# Sheet6.net
KiCad netlist of a schematic drawn in Altium Designer
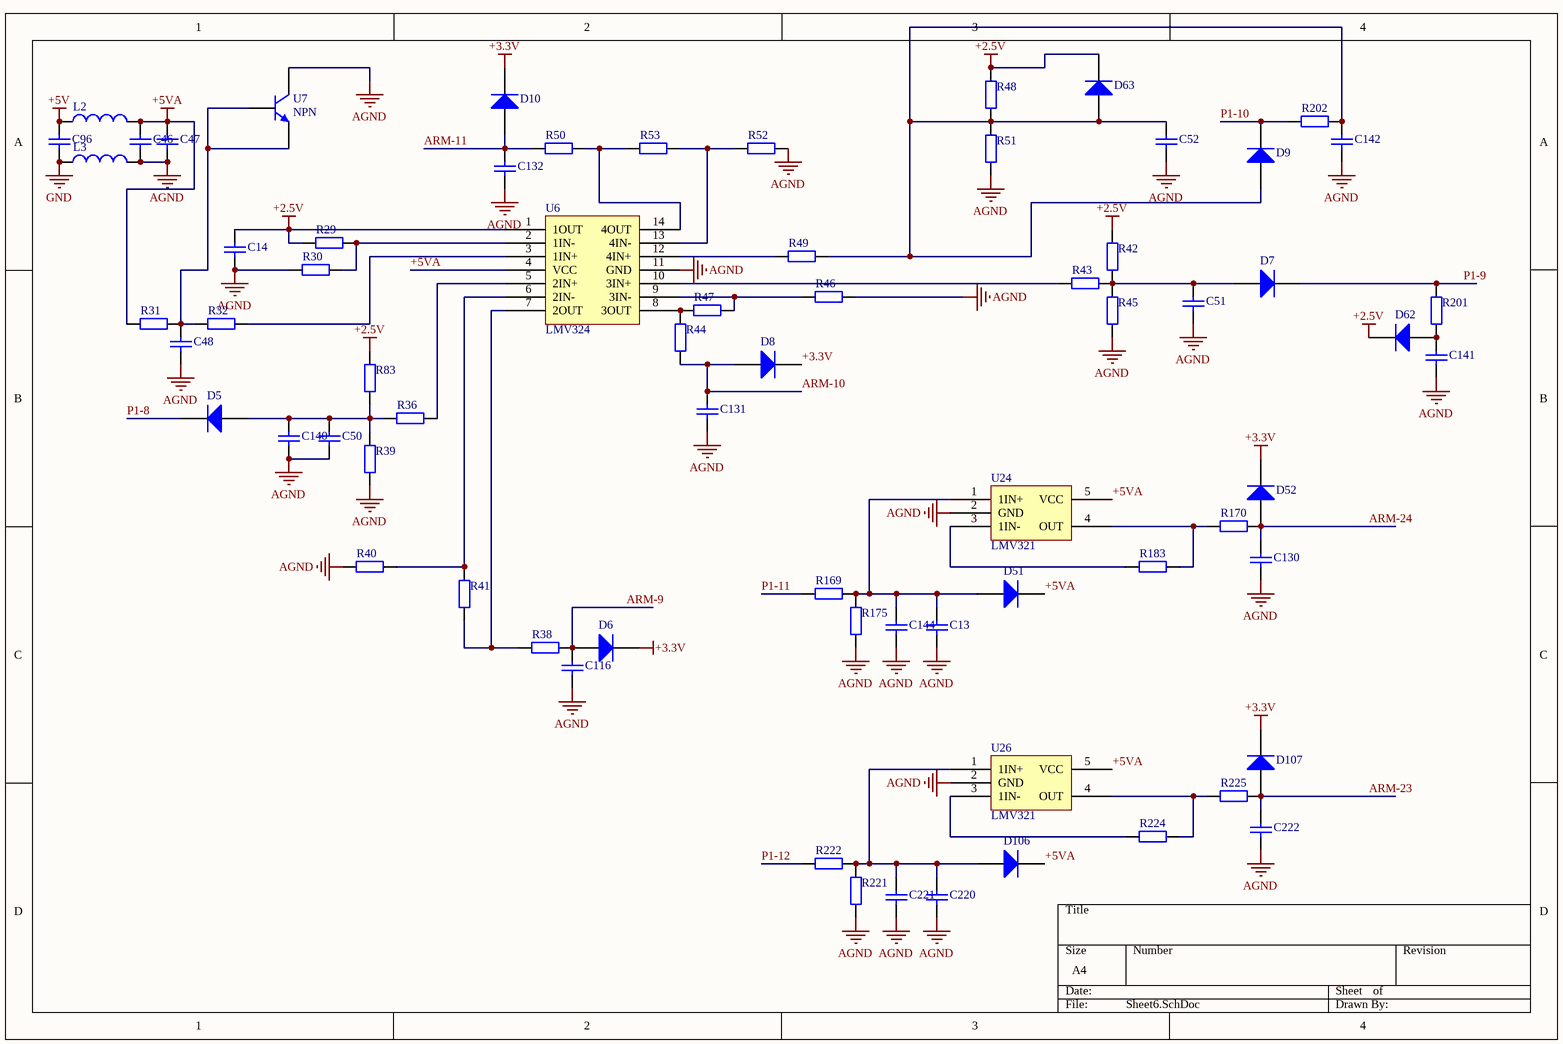
[diagram p0: Sheet6.SchDoc]

(export (version "E")
  (design (tool "Eeschema 10.0.6"))
  (components
    (comp (ref "C13")
      (value "Cap")
      (footprint "RAD-0.3")
      (description "Capacitor")
      (fields (field (name "PUBLISHER") "Altium Limited"))
      (libsource (lib "Miscellaneous Devices") (part "Cap"))
    )
    (comp (ref "C14")
      (value "Cap")
      (footprint "RAD-0.3")
      (description "Capacitor")
      (fields (field (name "PUBLISHER") "Altium Limited"))
      (libsource (lib "Miscellaneous Devices") (part "Cap"))
    )
    (comp (ref "C46")
      (value "Cap")
      (footprint "RAD-0.3")
      (description "Capacitor")
      (fields (field (name "PUBLISHER") "Altium Limited"))
      (libsource (lib "Miscellaneous Devices") (part "Cap"))
    )
    (comp (ref "C47")
      (value "Cap")
      (footprint "RAD-0.3")
      (description "Capacitor")
      (fields (field (name "PUBLISHER") "Altium Limited"))
      (libsource (lib "Miscellaneous Devices") (part "Cap"))
    )
    (comp (ref "C48")
      (value "Cap")
      (footprint "RAD-0.3")
      (description "Capacitor")
      (fields (field (name "PUBLISHER") "Altium Limited"))
      (libsource (lib "Miscellaneous Devices") (part "Cap"))
    )
    (comp (ref "C50")
      (value "Cap")
      (footprint "RAD-0.3")
      (description "Capacitor")
      (fields (field (name "PUBLISHER") "Altium Limited"))
      (libsource (lib "Miscellaneous Devices") (part "Cap"))
    )
    (comp (ref "C51")
      (value "Cap")
      (footprint "RAD-0.3")
      (description "Capacitor")
      (fields (field (name "PUBLISHER") "Altium Limited"))
      (libsource (lib "Miscellaneous Devices") (part "Cap"))
    )
    (comp (ref "C52")
      (value "Cap")
      (footprint "RAD-0.3")
      (description "Capacitor")
      (fields (field (name "PUBLISHER") "Altium Limited"))
      (libsource (lib "Miscellaneous Devices") (part "Cap"))
    )
    (comp (ref "C96")
      (value "Cap")
      (footprint "RAD-0.3")
      (description "Capacitor")
      (fields (field (name "PUBLISHER") "Altium Limited"))
      (libsource (lib "Miscellaneous Devices") (part "Cap"))
    )
    (comp (ref "C116")
      (value "Cap")
      (footprint "RAD-0.3")
      (description "Capacitor")
      (fields (field (name "PUBLISHER") "Altium Limited"))
      (libsource (lib "Miscellaneous Devices") (part "Cap"))
    )
    (comp (ref "C130")
      (value "Cap")
      (footprint "RAD-0.3")
      (description "Capacitor")
      (fields (field (name "PUBLISHER") "Altium Limited"))
      (libsource (lib "Miscellaneous Devices") (part "Cap"))
    )
    (comp (ref "C131")
      (value "Cap")
      (footprint "RAD-0.3")
      (description "Capacitor")
      (fields (field (name "PUBLISHER") "Altium Limited"))
      (libsource (lib "Miscellaneous Devices") (part "Cap"))
    )
    (comp (ref "C132")
      (value "Cap")
      (footprint "RAD-0.3")
      (description "Capacitor")
      (fields (field (name "PUBLISHER") "Altium Limited"))
      (libsource (lib "Miscellaneous Devices") (part "Cap"))
    )
    (comp (ref "C140")
      (value "Cap")
      (footprint "RAD-0.3")
      (description "Capacitor")
      (fields (field (name "PUBLISHER") "Altium Limited"))
      (libsource (lib "Miscellaneous Devices") (part "Cap"))
    )
    (comp (ref "C141")
      (value "Cap")
      (footprint "RAD-0.3")
      (description "Capacitor")
      (fields (field (name "PUBLISHER") "Altium Limited"))
      (libsource (lib "Miscellaneous Devices") (part "Cap"))
    )
    (comp (ref "C142")
      (value "Cap")
      (footprint "RAD-0.3")
      (description "Capacitor")
      (fields (field (name "PUBLISHER") "Altium Limited"))
      (libsource (lib "Miscellaneous Devices") (part "Cap"))
    )
    (comp (ref "C144")
      (value "Cap")
      (footprint "RAD-0.3")
      (description "Capacitor")
      (fields (field (name "PUBLISHER") "Altium Limited"))
      (libsource (lib "Miscellaneous Devices") (part "Cap"))
    )
    (comp (ref "C220")
      (value "Cap")
      (footprint "RAD-0.3")
      (description "Capacitor")
      (fields (field (name "PUBLISHER") "Altium Limited"))
      (libsource (lib "Miscellaneous Devices") (part "Cap"))
    )
    (comp (ref "C221")
      (value "Cap")
      (footprint "RAD-0.3")
      (description "Capacitor")
      (fields (field (name "PUBLISHER") "Altium Limited"))
      (libsource (lib "Miscellaneous Devices") (part "Cap"))
    )
    (comp (ref "C222")
      (value "Cap")
      (footprint "RAD-0.3")
      (description "Capacitor")
      (fields (field (name "PUBLISHER") "Altium Limited"))
      (libsource (lib "Miscellaneous Devices") (part "Cap"))
    )
    (comp (ref "D5")
      (value "Diode 1N4007")
      (footprint "DO-41")
      (description "1 Amp General Purpose Rectifier")
      (fields (field (name "PUBLISHER") "Altium Limited"))
      (libsource (lib "Miscellaneous Devices") (part "Diode 1N4007"))
    )
    (comp (ref "D6")
      (value "Diode 1N4007")
      (footprint "DO-41")
      (description "1 Amp General Purpose Rectifier")
      (fields (field (name "PUBLISHER") "Altium Limited"))
      (libsource (lib "Miscellaneous Devices") (part "Diode 1N4007"))
    )
    (comp (ref "D7")
      (value "Diode 1N4007")
      (footprint "DO-41")
      (description "1 Amp General Purpose Rectifier")
      (fields (field (name "PUBLISHER") "Altium Limited"))
      (libsource (lib "Miscellaneous Devices") (part "Diode 1N4007"))
    )
    (comp (ref "D8")
      (value "Diode 1N4007")
      (footprint "DO-41")
      (description "1 Amp General Purpose Rectifier")
      (fields (field (name "PUBLISHER") "Altium Limited"))
      (libsource (lib "Miscellaneous Devices") (part "Diode 1N4007"))
    )
    (comp (ref "D9")
      (value "Diode 1N4007")
      (footprint "DO-41")
      (description "1 Amp General Purpose Rectifier")
      (fields (field (name "PUBLISHER") "Altium Limited"))
      (libsource (lib "Miscellaneous Devices") (part "Diode 1N4007"))
    )
    (comp (ref "D10")
      (value "Diode 1N4007")
      (footprint "DO-41")
      (description "1 Amp General Purpose Rectifier")
      (fields (field (name "PUBLISHER") "Altium Limited"))
      (libsource (lib "Miscellaneous Devices") (part "Diode 1N4007"))
    )
    (comp (ref "D51")
      (value "Diode 1N4007")
      (footprint "DO-41")
      (description "1 Amp General Purpose Rectifier")
      (fields (field (name "PUBLISHER") "Altium Limited"))
      (libsource (lib "Miscellaneous Devices") (part "Diode 1N4007"))
    )
    (comp (ref "D52")
      (value "Diode 1N4007")
      (footprint "DO-41")
      (description "1 Amp General Purpose Rectifier")
      (fields (field (name "PUBLISHER") "Altium Limited"))
      (libsource (lib "Miscellaneous Devices") (part "Diode 1N4007"))
    )
    (comp (ref "D62")
      (value "Diode 1N4007")
      (footprint "DO-41")
      (description "1 Amp General Purpose Rectifier")
      (fields (field (name "PUBLISHER") "Altium Limited"))
      (libsource (lib "Miscellaneous Devices") (part "Diode 1N4007"))
    )
    (comp (ref "D63")
      (value "Diode 1N4007")
      (footprint "DO-41")
      (description "1 Amp General Purpose Rectifier")
      (fields (field (name "PUBLISHER") "Altium Limited"))
      (libsource (lib "Miscellaneous Devices") (part "Diode 1N4007"))
    )
    (comp (ref "D106")
      (value "Diode 1N4007")
      (footprint "DO-41")
      (description "1 Amp General Purpose Rectifier")
      (fields (field (name "PUBLISHER") "Altium Limited"))
      (libsource (lib "Miscellaneous Devices") (part "Diode 1N4007"))
    )
    (comp (ref "D107")
      (value "Diode 1N4007")
      (footprint "DO-41")
      (description "1 Amp General Purpose Rectifier")
      (fields (field (name "PUBLISHER") "Altium Limited"))
      (libsource (lib "Miscellaneous Devices") (part "Diode 1N4007"))
    )
    (comp (ref "L2")
      (value "Inductor")
      (footprint "0402-A")
      (fields (field (name "PUBLISHER") "Altium Limited"))
      (libsource (lib "Miscellaneous Devices") (part "Inductor"))
    )
    (comp (ref "L3")
      (value "Inductor")
      (footprint "0402-A")
      (fields (field (name "PUBLISHER") "Altium Limited"))
      (libsource (lib "Miscellaneous Devices") (part "Inductor"))
    )
    (comp (ref "R29")
      (value "Res2")
      (footprint "AXIAL-0.4")
      (description "Resistor")
      (fields (field (name "PUBLISHER") "Altium Limited"))
      (libsource (lib "Miscellaneous Devices") (part "Res2"))
    )
    (comp (ref "R30")
      (value "Res2")
      (footprint "AXIAL-0.4")
      (description "Resistor")
      (fields (field (name "PUBLISHER") "Altium Limited"))
      (libsource (lib "Miscellaneous Devices") (part "Res2"))
    )
    (comp (ref "R31")
      (value "Res2")
      (footprint "AXIAL-0.4")
      (description "Resistor")
      (fields (field (name "PUBLISHER") "Altium Limited"))
      (libsource (lib "Miscellaneous Devices") (part "Res2"))
    )
    (comp (ref "R32")
      (value "Res2")
      (footprint "AXIAL-0.4")
      (description "Resistor")
      (fields (field (name "PUBLISHER") "Altium Limited"))
      (libsource (lib "Miscellaneous Devices") (part "Res2"))
    )
    (comp (ref "R36")
      (value "Res2")
      (footprint "AXIAL-0.4")
      (description "Resistor")
      (fields (field (name "PUBLISHER") "Altium Limited"))
      (libsource (lib "Miscellaneous Devices") (part "Res2"))
    )
    (comp (ref "R38")
      (value "Res2")
      (footprint "AXIAL-0.4")
      (description "Resistor")
      (fields (field (name "PUBLISHER") "Altium Limited"))
      (libsource (lib "") (part "Res2_2"))
    )
    (comp (ref "R39")
      (value "Res2")
      (footprint "AXIAL-0.4")
      (description "Resistor")
      (fields (field (name "PUBLISHER") "Altium Limited"))
      (libsource (lib "") (part "Res2_1"))
    )
    (comp (ref "R40")
      (value "Res2")
      (footprint "AXIAL-0.4")
      (description "Resistor")
      (fields (field (name "PUBLISHER") "Altium Limited"))
      (libsource (lib "Miscellaneous Devices") (part "Res2"))
    )
    (comp (ref "R41")
      (value "Res2")
      (footprint "AXIAL-0.4")
      (description "Resistor")
      (fields (field (name "PUBLISHER") "Altium Limited"))
      (libsource (lib "") (part "Res2_1"))
    )
    (comp (ref "R42")
      (value "Res2")
      (footprint "AXIAL-0.4")
      (description "Resistor")
      (fields (field (name "PUBLISHER") "Altium Limited"))
      (libsource (lib "") (part "Res2_1"))
    )
    (comp (ref "R43")
      (value "Res2")
      (footprint "AXIAL-0.4")
      (description "Resistor")
      (fields (field (name "PUBLISHER") "Altium Limited"))
      (libsource (lib "Miscellaneous Devices") (part "Res2"))
    )
    (comp (ref "R44")
      (value "Res2")
      (footprint "AXIAL-0.4")
      (description "Resistor")
      (fields (field (name "PUBLISHER") "Altium Limited"))
      (libsource (lib "") (part "Res2_1"))
    )
    (comp (ref "R45")
      (value "Res2")
      (footprint "AXIAL-0.4")
      (description "Resistor")
      (fields (field (name "PUBLISHER") "Altium Limited"))
      (libsource (lib "") (part "Res2_1"))
    )
    (comp (ref "R46")
      (value "Res2")
      (footprint "AXIAL-0.4")
      (description "Resistor")
      (fields (field (name "PUBLISHER") "Altium Limited"))
      (libsource (lib "Miscellaneous Devices") (part "Res2"))
    )
    (comp (ref "R47")
      (value "Res2")
      (footprint "AXIAL-0.4")
      (description "Resistor")
      (fields (field (name "PUBLISHER") "Altium Limited"))
      (libsource (lib "Miscellaneous Devices") (part "Res2"))
    )
    (comp (ref "R48")
      (value "Res2")
      (footprint "AXIAL-0.4")
      (description "Resistor")
      (fields (field (name "PUBLISHER") "Altium Limited"))
      (libsource (lib "") (part "Res2_1"))
    )
    (comp (ref "R49")
      (value "Res2")
      (footprint "AXIAL-0.4")
      (description "Resistor")
      (fields (field (name "PUBLISHER") "Altium Limited"))
      (libsource (lib "Miscellaneous Devices") (part "Res2"))
    )
    (comp (ref "R50")
      (value "Res2")
      (footprint "AXIAL-0.4")
      (description "Resistor")
      (fields (field (name "PUBLISHER") "Altium Limited"))
      (libsource (lib "Miscellaneous Devices") (part "Res2"))
    )
    (comp (ref "R51")
      (value "Res2")
      (footprint "AXIAL-0.4")
      (description "Resistor")
      (fields (field (name "PUBLISHER") "Altium Limited"))
      (libsource (lib "") (part "Res2_1"))
    )
    (comp (ref "R52")
      (value "Res2")
      (footprint "AXIAL-0.4")
      (description "Resistor")
      (fields (field (name "PUBLISHER") "Altium Limited"))
      (libsource (lib "Miscellaneous Devices") (part "Res2"))
    )
    (comp (ref "R53")
      (value "Res2")
      (footprint "AXIAL-0.4")
      (description "Resistor")
      (fields (field (name "PUBLISHER") "Altium Limited"))
      (libsource (lib "Miscellaneous Devices") (part "Res2"))
    )
    (comp (ref "R83")
      (value "Res2")
      (footprint "AXIAL-0.4")
      (description "Resistor")
      (fields (field (name "PUBLISHER") "Altium Limited"))
      (libsource (lib "") (part "Res2_1"))
    )
    (comp (ref "R169")
      (value "Res2")
      (footprint "AXIAL-0.4")
      (description "Resistor")
      (fields (field (name "PUBLISHER") "Altium Limited"))
      (libsource (lib "Miscellaneous Devices") (part "Res2"))
    )
    (comp (ref "R170")
      (value "Res2")
      (footprint "AXIAL-0.4")
      (description "Resistor")
      (fields (field (name "PUBLISHER") "Altium Limited"))
      (libsource (lib "Miscellaneous Devices") (part "Res2"))
    )
    (comp (ref "R175")
      (value "Res2")
      (footprint "AXIAL-0.4")
      (description "Resistor")
      (fields (field (name "PUBLISHER") "Altium Limited"))
      (libsource (lib "") (part "Res2_1"))
    )
    (comp (ref "R183")
      (value "Res2")
      (footprint "AXIAL-0.4")
      (description "Resistor")
      (fields (field (name "PUBLISHER") "Altium Limited"))
      (libsource (lib "Miscellaneous Devices") (part "Res2"))
    )
    (comp (ref "R201")
      (value "Res2")
      (footprint "AXIAL-0.4")
      (description "Resistor")
      (fields (field (name "PUBLISHER") "Altium Limited"))
      (libsource (lib "") (part "Res2_1"))
    )
    (comp (ref "R202")
      (value "Res2")
      (footprint "AXIAL-0.4")
      (description "Resistor")
      (fields (field (name "PUBLISHER") "Altium Limited"))
      (libsource (lib "") (part "Res2_2"))
    )
    (comp (ref "R221")
      (value "Res2")
      (footprint "AXIAL-0.4")
      (description "Resistor")
      (fields (field (name "PUBLISHER") "Altium Limited"))
      (libsource (lib "") (part "Res2_1"))
    )
    (comp (ref "R222")
      (value "Res2")
      (footprint "AXIAL-0.4")
      (description "Resistor")
      (fields (field (name "PUBLISHER") "Altium Limited"))
      (libsource (lib "Miscellaneous Devices") (part "Res2"))
    )
    (comp (ref "R224")
      (value "Res2")
      (footprint "AXIAL-0.4")
      (description "Resistor")
      (fields (field (name "PUBLISHER") "Altium Limited"))
      (libsource (lib "Miscellaneous Devices") (part "Res2"))
    )
    (comp (ref "R225")
      (value "Res2")
      (footprint "AXIAL-0.4")
      (description "Resistor")
      (fields (field (name "PUBLISHER") "Altium Limited"))
      (libsource (lib "Miscellaneous Devices") (part "Res2"))
    )
    (comp (ref "U6") (value "LMV324") (libsource (lib "LMV324") (part "Component_1")))
    (comp (ref "U7")
      (value "NPN")
      (footprint "TO-226")
      (description "NPN Bipolar Transistor")
      (fields (field (name "PUBLISHER") "Altium Limited"))
      (libsource (lib "Miscellaneous Devices") (part "NPN"))
    )
    (comp (ref "U24") (value "LMV321") (libsource (lib "LMV321") (part "Component_1")))
    (comp (ref "U26") (value "LMV321") (libsource (lib "LMV321") (part "Component_1")))
  )
  (nets
    (net (code "1") (name "+2.5V") (class "Default")
      (node (ref "C14") (pin "2") (pinfunction "2_2") (pintype "passive"))
      (node (ref "D62") (pin "2") (pinfunction "K_2") (pintype "passive"))
      (node (ref "D63") (pin "2") (pinfunction "K_2") (pintype "passive"))
      (node (ref "R29") (pin "2") (pinfunction "2_2") (pintype "passive"))
      (node (ref "R42") (pin "1") (pinfunction "1_1") (pintype "passive"))
      (node (ref "R48") (pin "1") (pinfunction "1_1") (pintype "passive"))
      (node (ref "R83") (pin "1") (pinfunction "1_1") (pintype "passive"))
      (node (ref "U6") (pin "1") (pinfunction "1OUT_1") (pintype "passive"))
    )
    (net (code "2") (name "+3.3V") (class "Default")
      (node (ref "D10") (pin "2") (pinfunction "K_2") (pintype "passive"))
      (node (ref "D107") (pin "2") (pinfunction "K_2") (pintype "passive"))
      (node (ref "D52") (pin "2") (pinfunction "K_2") (pintype "passive"))
      (node (ref "D6") (pin "2") (pinfunction "K_2") (pintype "passive"))
      (node (ref "D8") (pin "2") (pinfunction "K_2") (pintype "passive"))
    )
    (net (code "3") (name "+5V") (class "Default")
      (node (ref "C96") (pin "2") (pinfunction "2_2") (pintype "passive"))
      (node (ref "L2") (pin "1") (pinfunction "1_1") (pintype "passive"))
    )
    (net (code "4") (name "+5VA") (class "Default")
      (node (ref "C46") (pin "2") (pinfunction "2_2") (pintype "passive"))
      (node (ref "C47") (pin "2") (pinfunction "2_2") (pintype "passive"))
      (node (ref "D106") (pin "2") (pinfunction "K_2") (pintype "passive"))
      (node (ref "D51") (pin "2") (pinfunction "K_2") (pintype "passive"))
      (node (ref "L2") (pin "2") (pinfunction "2_2") (pintype "passive"))
      (node (ref "R31") (pin "2") (pinfunction "2_2") (pintype "passive"))
      (node (ref "U24") (pin "5") (pinfunction "VCC_5") (pintype "passive"))
      (node (ref "U26") (pin "5") (pinfunction "VCC_5") (pintype "passive"))
      (node (ref "U6") (pin "4") (pinfunction "VCC_4") (pintype "passive"))
    )
    (net (code "5") (name "/ARM-9") (class "Default")
      (node (ref "C116") (pin "2") (pinfunction "2_2") (pintype "passive"))
      (node (ref "D6") (pin "1") (pinfunction "A_1") (pintype "passive"))
      (node (ref "R38") (pin "2") (pinfunction "2_2") (pintype "passive"))
    )
    (net (code "6") (name "/ARM-10") (class "Default")
      (node (ref "C131") (pin "2") (pinfunction "2_2") (pintype "passive"))
      (node (ref "D8") (pin "1") (pinfunction "A_1") (pintype "passive"))
      (node (ref "R44") (pin "2") (pinfunction "2_2") (pintype "passive"))
    )
    (net (code "7") (name "/ARM-11") (class "Default")
      (node (ref "C132") (pin "2") (pinfunction "2_2") (pintype "passive"))
      (node (ref "D10") (pin "1") (pinfunction "A_1") (pintype "passive"))
      (node (ref "R50") (pin "2") (pinfunction "2_2") (pintype "passive"))
    )
    (net (code "8") (name "/ARM-23") (class "Default")
      (node (ref "C222") (pin "2") (pinfunction "2_2") (pintype "passive"))
      (node (ref "D107") (pin "1") (pinfunction "A_1") (pintype "passive"))
      (node (ref "R225") (pin "1") (pinfunction "1_1") (pintype "passive"))
    )
    (net (code "9") (name "/ARM-24") (class "Default")
      (node (ref "C130") (pin "2") (pinfunction "2_2") (pintype "passive"))
      (node (ref "D52") (pin "1") (pinfunction "A_1") (pintype "passive"))
      (node (ref "R170") (pin "1") (pinfunction "1_1") (pintype "passive"))
    )
    (net (code "10") (name "/P1-8") (class "Default")
      (node (ref "D5") (pin "2") (pinfunction "K_2") (pintype "passive"))
    )
    (net (code "11") (name "/P1-9") (class "Default")
      (node (ref "D7") (pin "2") (pinfunction "K_2") (pintype "passive"))
      (node (ref "R201") (pin "1") (pinfunction "1_1") (pintype "passive"))
    )
    (net (code "12") (name "/P1-10") (class "Default")
      (node (ref "D9") (pin "2") (pinfunction "K_2") (pintype "passive"))
      (node (ref "R202") (pin "1") (pinfunction "1_1") (pintype "passive"))
    )
    (net (code "13") (name "/P1-11") (class "Default")
      (node (ref "R169") (pin "2") (pinfunction "2_2") (pintype "passive"))
    )
    (net (code "14") (name "/P1-12") (class "Default")
      (node (ref "R222") (pin "2") (pinfunction "2_2") (pintype "passive"))
    )
    (net (code "15") (name "AGND") (class "Default")
      (node (ref "C116") (pin "1") (pinfunction "1_1") (pintype "passive"))
      (node (ref "C13") (pin "1") (pinfunction "1_1") (pintype "passive"))
      (node (ref "C130") (pin "1") (pinfunction "1_1") (pintype "passive"))
      (node (ref "C131") (pin "1") (pinfunction "1_1") (pintype "passive"))
      (node (ref "C132") (pin "1") (pinfunction "1_1") (pintype "passive"))
      (node (ref "C14") (pin "1") (pinfunction "1_1") (pintype "passive"))
      (node (ref "C140") (pin "1") (pinfunction "1_1") (pintype "passive"))
      (node (ref "C141") (pin "1") (pinfunction "1_1") (pintype "passive"))
      (node (ref "C142") (pin "1") (pinfunction "1_1") (pintype "passive"))
      (node (ref "C144") (pin "1") (pinfunction "1_1") (pintype "passive"))
      (node (ref "C220") (pin "1") (pinfunction "1_1") (pintype "passive"))
      (node (ref "C221") (pin "1") (pinfunction "1_1") (pintype "passive"))
      (node (ref "C222") (pin "1") (pinfunction "1_1") (pintype "passive"))
      (node (ref "C46") (pin "1") (pinfunction "1_1") (pintype "passive"))
      (node (ref "C47") (pin "1") (pinfunction "1_1") (pintype "passive"))
      (node (ref "C48") (pin "1") (pinfunction "1_1") (pintype "passive"))
      (node (ref "C50") (pin "1") (pinfunction "1_1") (pintype "passive"))
      (node (ref "C51") (pin "1") (pinfunction "1_1") (pintype "passive"))
      (node (ref "C52") (pin "1") (pinfunction "1_1") (pintype "passive"))
      (node (ref "L3") (pin "2") (pinfunction "2_2") (pintype "passive"))
      (node (ref "R175") (pin "2") (pinfunction "2_2") (pintype "passive"))
      (node (ref "R221") (pin "2") (pinfunction "2_2") (pintype "passive"))
      (node (ref "R30") (pin "2") (pinfunction "2_2") (pintype "passive"))
      (node (ref "R39") (pin "2") (pinfunction "2_2") (pintype "passive"))
      (node (ref "R40") (pin "2") (pinfunction "2_2") (pintype "passive"))
      (node (ref "R45") (pin "2") (pinfunction "2_2") (pintype "passive"))
      (node (ref "R46") (pin "1") (pinfunction "1_1") (pintype "passive"))
      (node (ref "R51") (pin "2") (pinfunction "2_2") (pintype "passive"))
      (node (ref "R52") (pin "1") (pinfunction "1_1") (pintype "passive"))
      (node (ref "U24") (pin "2") (pinfunction "GND_2") (pintype "passive"))
      (node (ref "U26") (pin "2") (pinfunction "GND_2") (pintype "passive"))
      (node (ref "U6") (pin "11") (pinfunction "GND_11") (pintype "passive"))
      (node (ref "U7") (pin "1") (pinfunction "C_1") (pintype "passive"))
    )
    (net (code "16") (name "GND") (class "Default")
      (node (ref "C96") (pin "1") (pinfunction "1_1") (pintype "passive"))
      (node (ref "L3") (pin "1") (pinfunction "1_1") (pintype "passive"))
    )
    (net (code "17") (name "Net-(D5-A)") (class "Default")
      (node (ref "C140") (pin "2") (pinfunction "2_2") (pintype "passive"))
      (node (ref "C50") (pin "2") (pinfunction "2_2") (pintype "passive"))
      (node (ref "D5") (pin "1") (pinfunction "A_1") (pintype "passive"))
      (node (ref "R36") (pin "2") (pinfunction "2_2") (pintype "passive"))
      (node (ref "R39") (pin "1") (pinfunction "1_1") (pintype "passive"))
      (node (ref "R83") (pin "2") (pinfunction "2_2") (pintype "passive"))
    )
    (net (code "18") (name "Net-(D7-A)") (class "Default")
      (node (ref "C51") (pin "2") (pinfunction "2_2") (pintype "passive"))
      (node (ref "D7") (pin "1") (pinfunction "A_1") (pintype "passive"))
      (node (ref "R42") (pin "2") (pinfunction "2_2") (pintype "passive"))
      (node (ref "R43") (pin "1") (pinfunction "1_1") (pintype "passive"))
      (node (ref "R45") (pin "1") (pinfunction "1_1") (pintype "passive"))
    )
    (net (code "19") (name "Net-(D51-A)") (class "Default")
      (node (ref "C13") (pin "2") (pinfunction "2_2") (pintype "passive"))
      (node (ref "C144") (pin "2") (pinfunction "2_2") (pintype "passive"))
      (node (ref "D51") (pin "1") (pinfunction "A_1") (pintype "passive"))
      (node (ref "R169") (pin "1") (pinfunction "1_1") (pintype "passive"))
      (node (ref "R175") (pin "1") (pinfunction "1_1") (pintype "passive"))
      (node (ref "U24") (pin "1") (pinfunction "1IN+_1") (pintype "passive"))
    )
    (net (code "20") (name "Net-(D62-A)") (class "Default")
      (node (ref "C141") (pin "2") (pinfunction "2_2") (pintype "passive"))
      (node (ref "D62") (pin "1") (pinfunction "A_1") (pintype "passive"))
      (node (ref "R201") (pin "2") (pinfunction "2_2") (pintype "passive"))
    )
    (net (code "21") (name "Net-(D63-A)") (class "Default")
      (node (ref "C142") (pin "2") (pinfunction "2_2") (pintype "passive"))
      (node (ref "C52") (pin "2") (pinfunction "2_2") (pintype "passive"))
      (node (ref "D63") (pin "1") (pinfunction "A_1") (pintype "passive"))
      (node (ref "D9") (pin "1") (pinfunction "A_1") (pintype "passive"))
      (node (ref "R202") (pin "2") (pinfunction "2_2") (pintype "passive"))
      (node (ref "R48") (pin "2") (pinfunction "2_2") (pintype "passive"))
      (node (ref "R49") (pin "1") (pinfunction "1_1") (pintype "passive"))
      (node (ref "R51") (pin "1") (pinfunction "1_1") (pintype "passive"))
    )
    (net (code "22") (name "Net-(D106-A)") (class "Default")
      (node (ref "C220") (pin "2") (pinfunction "2_2") (pintype "passive"))
      (node (ref "C221") (pin "2") (pinfunction "2_2") (pintype "passive"))
      (node (ref "D106") (pin "1") (pinfunction "A_1") (pintype "passive"))
      (node (ref "R221") (pin "1") (pinfunction "1_1") (pintype "passive"))
      (node (ref "R222") (pin "1") (pinfunction "1_1") (pintype "passive"))
      (node (ref "U26") (pin "1") (pinfunction "1IN+_1") (pintype "passive"))
    )
    (net (code "23") (name "Net-(U6-1IN+)") (class "Default")
      (node (ref "R32") (pin "1") (pinfunction "1_1") (pintype "passive"))
      (node (ref "U6") (pin "3") (pinfunction "1IN+_3") (pintype "passive"))
    )
    (net (code "24") (name "Net-(U6-1IN-)") (class "Default")
      (node (ref "R29") (pin "1") (pinfunction "1_1") (pintype "passive"))
      (node (ref "R30") (pin "1") (pinfunction "1_1") (pintype "passive"))
      (node (ref "U6") (pin "2") (pinfunction "1IN-_2") (pintype "passive"))
    )
    (net (code "25") (name "Net-(U6-2IN+)") (class "Default")
      (node (ref "R36") (pin "1") (pinfunction "1_1") (pintype "passive"))
      (node (ref "U6") (pin "5") (pinfunction "2IN+_5") (pintype "passive"))
    )
    (net (code "26") (name "Net-(U6-2IN-)") (class "Default")
      (node (ref "R40") (pin "1") (pinfunction "1_1") (pintype "passive"))
      (node (ref "R41") (pin "1") (pinfunction "1_1") (pintype "passive"))
      (node (ref "U6") (pin "6") (pinfunction "2IN-_6") (pintype "passive"))
    )
    (net (code "27") (name "Net-(U6-2OUT)") (class "Default")
      (node (ref "R38") (pin "1") (pinfunction "1_1") (pintype "passive"))
      (node (ref "R41") (pin "2") (pinfunction "2_2") (pintype "passive"))
      (node (ref "U6") (pin "7") (pinfunction "2OUT_7") (pintype "passive"))
    )
    (net (code "28") (name "Net-(U6-3IN+)") (class "Default")
      (node (ref "R43") (pin "2") (pinfunction "2_2") (pintype "passive"))
      (node (ref "U6") (pin "10") (pinfunction "3IN+_10") (pintype "passive"))
    )
    (net (code "29") (name "Net-(U6-3IN-)") (class "Default")
      (node (ref "R46") (pin "2") (pinfunction "2_2") (pintype "passive"))
      (node (ref "R47") (pin "1") (pinfunction "1_1") (pintype "passive"))
      (node (ref "U6") (pin "9") (pinfunction "3IN-_9") (pintype "passive"))
    )
    (net (code "30") (name "Net-(U6-3OUT)") (class "Default")
      (node (ref "R44") (pin "1") (pinfunction "1_1") (pintype "passive"))
      (node (ref "R47") (pin "2") (pinfunction "2_2") (pintype "passive"))
      (node (ref "U6") (pin "8") (pinfunction "3OUT_8") (pintype "passive"))
    )
    (net (code "31") (name "Net-(U6-4IN+)") (class "Default")
      (node (ref "R49") (pin "2") (pinfunction "2_2") (pintype "passive"))
      (node (ref "U6") (pin "12") (pinfunction "4IN+_12") (pintype "passive"))
    )
    (net (code "32") (name "Net-(U6-4IN-)") (class "Default")
      (node (ref "R52") (pin "2") (pinfunction "2_2") (pintype "passive"))
      (node (ref "R53") (pin "1") (pinfunction "1_1") (pintype "passive"))
      (node (ref "U6") (pin "13") (pinfunction "4IN-_13") (pintype "passive"))
    )
    (net (code "33") (name "Net-(U6-4OUT)") (class "Default")
      (node (ref "R50") (pin "1") (pinfunction "1_1") (pintype "passive"))
      (node (ref "R53") (pin "2") (pinfunction "2_2") (pintype "passive"))
      (node (ref "U6") (pin "14") (pinfunction "4OUT_14") (pintype "passive"))
    )
    (net (code "34") (name "Net-(U7-B)") (class "Default")
      (node (ref "C48") (pin "2") (pinfunction "2_2") (pintype "passive"))
      (node (ref "R31") (pin "1") (pinfunction "1_1") (pintype "passive"))
      (node (ref "R32") (pin "2") (pinfunction "2_2") (pintype "passive"))
      (node (ref "U7") (pin "2") (pinfunction "B_2") (pintype "passive"))
      (node (ref "U7") (pin "3") (pinfunction "E_3") (pintype "passive"))
    )
    (net (code "35") (name "Net-(U24-1IN-)") (class "Default")
      (node (ref "R183") (pin "2") (pinfunction "2_2") (pintype "passive"))
      (node (ref "U24") (pin "3") (pinfunction "1IN-_3") (pintype "passive"))
    )
    (net (code "36") (name "Net-(U24-OUT)") (class "Default")
      (node (ref "R170") (pin "2") (pinfunction "2_2") (pintype "passive"))
      (node (ref "R183") (pin "1") (pinfunction "1_1") (pintype "passive"))
      (node (ref "U24") (pin "4") (pinfunction "OUT_4") (pintype "passive"))
    )
    (net (code "37") (name "Net-(U26-1IN-)") (class "Default")
      (node (ref "R224") (pin "2") (pinfunction "2_2") (pintype "passive"))
      (node (ref "U26") (pin "3") (pinfunction "1IN-_3") (pintype "passive"))
    )
    (net (code "38") (name "Net-(U26-OUT)") (class "Default")
      (node (ref "R224") (pin "1") (pinfunction "1_1") (pintype "passive"))
      (node (ref "R225") (pin "2") (pinfunction "2_2") (pintype "passive"))
      (node (ref "U26") (pin "4") (pinfunction "OUT_4") (pintype "passive"))
    )
  )
)
